# untitled.net
KiCad netlist of a schematic drawn in EAGLE
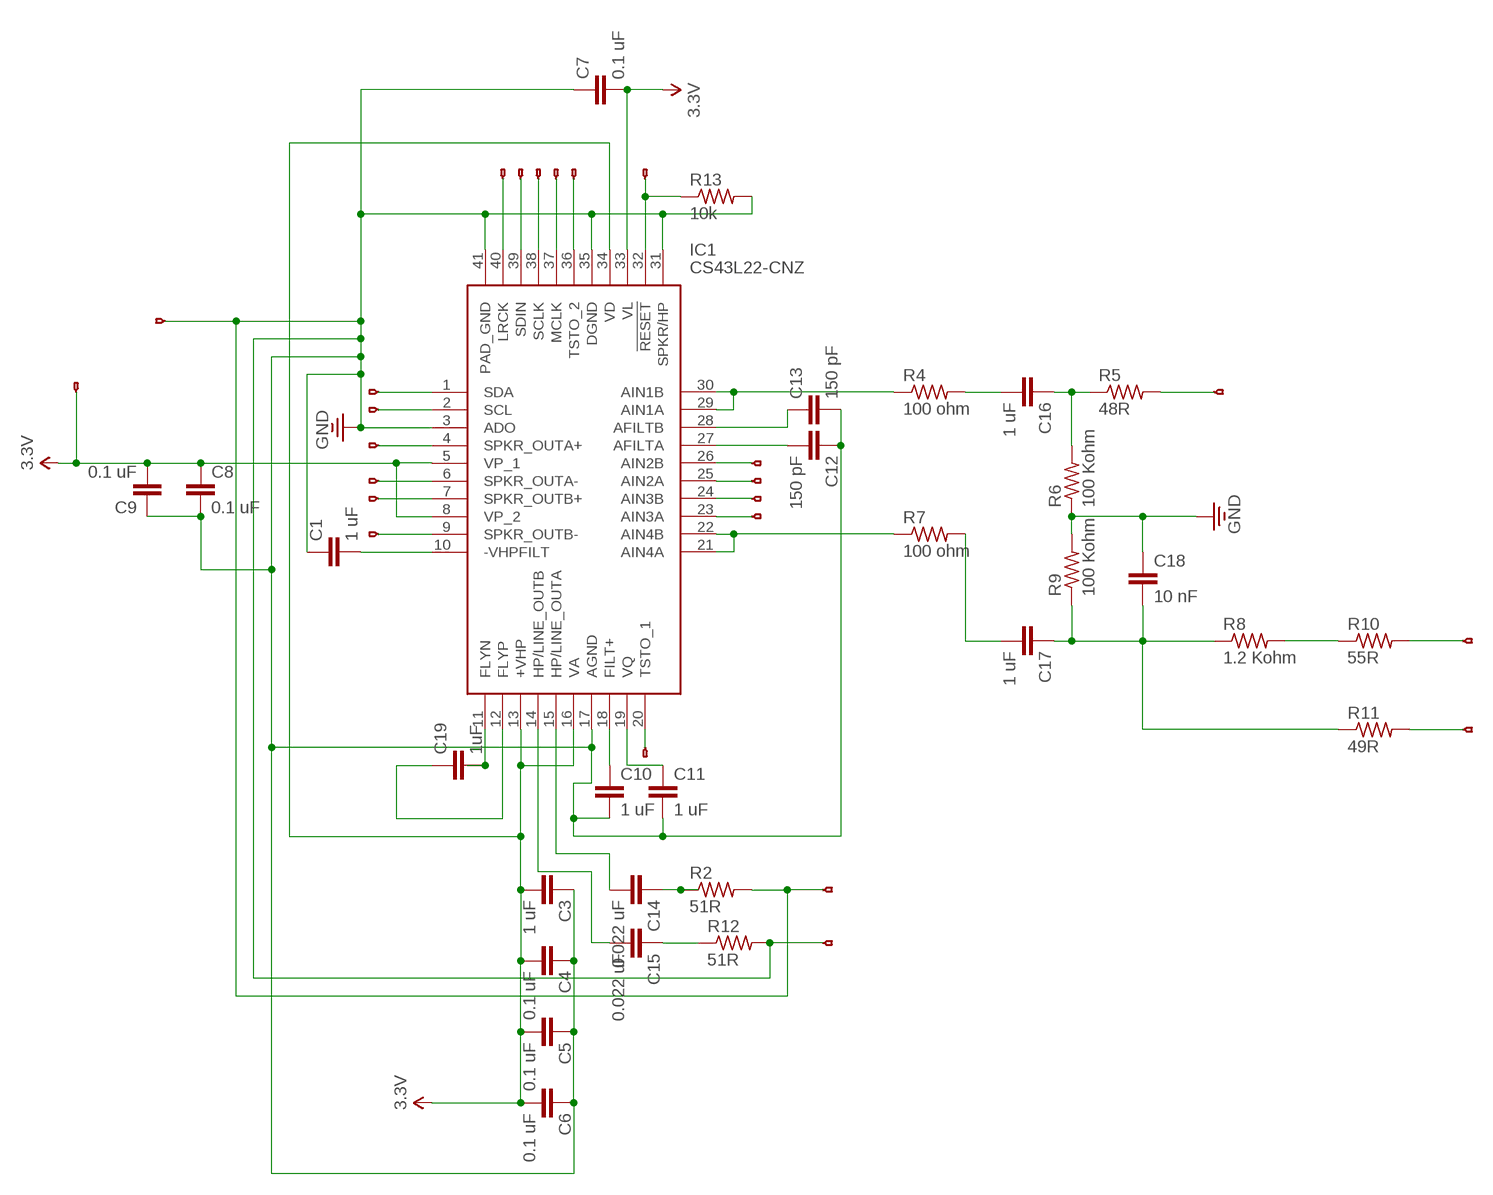
[diagram p0: schematic, sheet 1]

(export (version "E")
  (design (tool "Eeschema 10.0.6"))
  (components
    (comp (ref "C1")
      (value "1 uF")
      (footprint "eagle-import:CAP-PTH-SMALL-KIT")
      (libsource (lib "eagle-import") (part "CAPKIT"))
    )
    (comp (ref "C3")
      (value "1 uF")
      (footprint "eagle-import:CAP-PTH-SMALL-KIT")
      (libsource (lib "eagle-import") (part "CAPKIT"))
    )
    (comp (ref "C4")
      (value "0.1 uF")
      (footprint "eagle-import:CAP-PTH-SMALL-KIT")
      (libsource (lib "eagle-import") (part "CAPKIT"))
    )
    (comp (ref "C5")
      (value "0.1 uF")
      (footprint "eagle-import:CAP-PTH-SMALL-KIT")
      (libsource (lib "eagle-import") (part "CAPKIT"))
    )
    (comp (ref "C6")
      (value "0.1 uF")
      (footprint "eagle-import:CAP-PTH-SMALL-KIT")
      (libsource (lib "eagle-import") (part "CAPKIT"))
    )
    (comp (ref "C7")
      (value "0.1 uF")
      (footprint "eagle-import:CAP-PTH-SMALL-KIT")
      (libsource (lib "eagle-import") (part "CAPKIT"))
    )
    (comp (ref "C8")
      (value "0.1 uF")
      (footprint "eagle-import:CAP-PTH-SMALL-KIT")
      (libsource (lib "eagle-import") (part "CAPKIT"))
    )
    (comp (ref "C9")
      (value "0.1 uF")
      (footprint "eagle-import:CAP-PTH-SMALL-KIT")
      (libsource (lib "eagle-import") (part "CAPKIT"))
    )
    (comp (ref "C10")
      (value "1 uF")
      (footprint "eagle-import:CAP-PTH-SMALL-KIT")
      (libsource (lib "eagle-import") (part "CAPKIT"))
    )
    (comp (ref "C11")
      (value "1 uF")
      (footprint "eagle-import:CAP-PTH-SMALL-KIT")
      (libsource (lib "eagle-import") (part "CAPKIT"))
    )
    (comp (ref "C12")
      (value "150 pF")
      (footprint "eagle-import:CAP-PTH-SMALL-KIT")
      (libsource (lib "eagle-import") (part "CAPKIT"))
    )
    (comp (ref "C13")
      (value "150 pF")
      (footprint "eagle-import:CAP-PTH-SMALL-KIT")
      (libsource (lib "eagle-import") (part "CAPKIT"))
    )
    (comp (ref "C14")
      (value "0.022 uF")
      (footprint "eagle-import:CAP-PTH-SMALL-KIT")
      (libsource (lib "eagle-import") (part "CAPKIT"))
    )
    (comp (ref "C15")
      (value "0.022 uF")
      (footprint "eagle-import:CAP-PTH-SMALL-KIT")
      (libsource (lib "eagle-import") (part "CAPKIT"))
    )
    (comp (ref "C16")
      (value "1 uF")
      (footprint "eagle-import:CAP-PTH-SMALL-KIT")
      (libsource (lib "eagle-import") (part "CAPKIT"))
    )
    (comp (ref "C17")
      (value "1 uF")
      (footprint "eagle-import:CAP-PTH-SMALL-KIT")
      (libsource (lib "eagle-import") (part "CAPKIT"))
    )
    (comp (ref "C18")
      (value "10 nF")
      (footprint "eagle-import:CAP-PTH-SMALL-KIT")
      (libsource (lib "eagle-import") (part "CAPKIT"))
    )
    (comp (ref "C19")
      (value "1uF")
      (footprint "eagle-import:C2.5-3")
      (libsource (lib "eagle-import") (part "C2,5-3"))
    )
    (comp (ref "IC1")
      (value "CS43L22-CNZ")
      (footprint "eagle-import:QFN50P600X600X100-41N")
      (fields
        (field (name "MOUSER_PART_NUMBER") "777-CS43L22-CNZ")
        (field (name "RS_PART_NUMBER") "7165851P")
      )
      (libsource (lib "eagle-import") (part "CS43L22-CNZ"))
    )
    (comp (ref "JP1")
      (value "HEADERHOLE-HEADERHOLE")
      (footprint "eagle-import:1X1-HEADER-HOLE")
      (libsource (lib "eagle-import") (part "HEADERHOLE-HEADERHOLE"))
    )
    (comp (ref "JP2")
      (value "HEADERHOLE-HEADERHOLE")
      (footprint "eagle-import:1X1-HEADER-HOLE")
      (libsource (lib "eagle-import") (part "HEADERHOLE-HEADERHOLE"))
    )
    (comp (ref "JP3")
      (value "HEADERHOLE-HEADERHOLE")
      (footprint "eagle-import:1X1-HEADER-HOLE")
      (libsource (lib "eagle-import") (part "HEADERHOLE-HEADERHOLE"))
    )
    (comp (ref "JP4")
      (value "HEADERHOLE-HEADERHOLE")
      (footprint "eagle-import:1X1-HEADER-HOLE")
      (libsource (lib "eagle-import") (part "HEADERHOLE-HEADERHOLE"))
    )
    (comp (ref "JP5")
      (value "HEADERHOLE-HEADERHOLE")
      (footprint "eagle-import:1X1-HEADER-HOLE")
      (libsource (lib "eagle-import") (part "HEADERHOLE-HEADERHOLE"))
    )
    (comp (ref "JP6")
      (value "HEADERHOLE-HEADERHOLE")
      (footprint "eagle-import:1X1-HEADER-HOLE")
      (libsource (lib "eagle-import") (part "HEADERHOLE-HEADERHOLE"))
    )
    (comp (ref "JP7")
      (value "HEADERHOLE-HEADERHOLE")
      (footprint "eagle-import:1X1-HEADER-HOLE")
      (libsource (lib "eagle-import") (part "HEADERHOLE-HEADERHOLE"))
    )
    (comp (ref "JP8")
      (value "HEADERHOLE-HEADERHOLE")
      (footprint "eagle-import:1X1-HEADER-HOLE")
      (libsource (lib "eagle-import") (part "HEADERHOLE-HEADERHOLE"))
    )
    (comp (ref "JP9")
      (value "HEADERHOLE-HEADERHOLE")
      (footprint "eagle-import:1X1-HEADER-HOLE")
      (libsource (lib "eagle-import") (part "HEADERHOLE-HEADERHOLE"))
    )
    (comp (ref "JP10")
      (value "HEADERHOLE-HEADERHOLE")
      (footprint "eagle-import:1X1-HEADER-HOLE")
      (libsource (lib "eagle-import") (part "HEADERHOLE-HEADERHOLE"))
    )
    (comp (ref "JP11")
      (value "HEADERHOLE-HEADERHOLE")
      (footprint "eagle-import:1X1-HEADER-HOLE")
      (libsource (lib "eagle-import") (part "HEADERHOLE-HEADERHOLE"))
    )
    (comp (ref "JP12")
      (value "HEADERHOLE-HEADERHOLE")
      (footprint "eagle-import:1X1-HEADER-HOLE")
      (libsource (lib "eagle-import") (part "HEADERHOLE-HEADERHOLE"))
    )
    (comp (ref "JP13")
      (value "HEADERHOLE-HEADERHOLE")
      (footprint "eagle-import:1X1-HEADER-HOLE")
      (libsource (lib "eagle-import") (part "HEADERHOLE-HEADERHOLE"))
    )
    (comp (ref "JP14")
      (value "HEADERHOLE-HEADERHOLE")
      (footprint "eagle-import:1X1-HEADER-HOLE")
      (libsource (lib "eagle-import") (part "HEADERHOLE-HEADERHOLE"))
    )
    (comp (ref "JP15")
      (value "HEADERHOLE-HEADERHOLE")
      (footprint "eagle-import:1X1-HEADER-HOLE")
      (libsource (lib "eagle-import") (part "HEADERHOLE-HEADERHOLE"))
    )
    (comp (ref "JP16")
      (value "HEADERHOLE-HEADERHOLE")
      (footprint "eagle-import:1X1-HEADER-HOLE")
      (libsource (lib "eagle-import") (part "HEADERHOLE-HEADERHOLE"))
    )
    (comp (ref "JP17")
      (value "HEADERHOLE-HEADERHOLE")
      (footprint "eagle-import:1X1-HEADER-HOLE")
      (libsource (lib "eagle-import") (part "HEADERHOLE-HEADERHOLE"))
    )
    (comp (ref "JP18")
      (value "HEADERHOLE-HEADERHOLE")
      (footprint "eagle-import:1X1-HEADER-HOLE")
      (libsource (lib "eagle-import") (part "HEADERHOLE-HEADERHOLE"))
    )
    (comp (ref "JP19")
      (value "HEADERHOLE-HEADERHOLE")
      (footprint "eagle-import:1X1-HEADER-HOLE")
      (libsource (lib "eagle-import") (part "HEADERHOLE-HEADERHOLE"))
    )
    (comp (ref "JP20")
      (value "HEADERHOLE-HEADERHOLE")
      (footprint "eagle-import:1X1-HEADER-HOLE")
      (libsource (lib "eagle-import") (part "HEADERHOLE-HEADERHOLE"))
    )
    (comp (ref "JP21")
      (value "HEADERHOLE-HEADERHOLE")
      (footprint "eagle-import:1X1-HEADER-HOLE")
      (libsource (lib "eagle-import") (part "HEADERHOLE-HEADERHOLE"))
    )
    (comp (ref "JP22")
      (value "HEADERHOLE-HEADERHOLE")
      (footprint "eagle-import:1X1-HEADER-HOLE")
      (libsource (lib "eagle-import") (part "HEADERHOLE-HEADERHOLE"))
    )
    (comp (ref "JP23")
      (value "HEADERHOLE-HEADERHOLE")
      (footprint "eagle-import:1X1-HEADER-HOLE")
      (libsource (lib "eagle-import") (part "HEADERHOLE-HEADERHOLE"))
    )
    (comp (ref "JP24")
      (value "HEADERHOLE-HEADERHOLE")
      (footprint "eagle-import:1X1-HEADER-HOLE")
      (libsource (lib "eagle-import") (part "HEADERHOLE-HEADERHOLE"))
    )
    (comp (ref "R2")
      (value "51R")
      (footprint "eagle-import:0204V")
      (libsource (lib "eagle-import") (part "R-US_0204/2V"))
    )
    (comp (ref "R4")
      (value "100 ohm")
      (footprint "eagle-import:0204V")
      (libsource (lib "eagle-import") (part "R-US_0204/2V"))
    )
    (comp (ref "R5")
      (value "48R")
      (footprint "eagle-import:0204V")
      (libsource (lib "eagle-import") (part "R-US_0204/2V"))
    )
    (comp (ref "R6")
      (value "100 Kohm")
      (footprint "eagle-import:0204V")
      (libsource (lib "eagle-import") (part "R-US_0204/2V"))
    )
    (comp (ref "R7")
      (value "100 ohm")
      (footprint "eagle-import:0204V")
      (libsource (lib "eagle-import") (part "R-US_0204/2V"))
    )
    (comp (ref "R8")
      (value "1.2 Kohm")
      (footprint "eagle-import:0204V")
      (libsource (lib "eagle-import") (part "R-US_0204/2V"))
    )
    (comp (ref "R9")
      (value "100 Kohm")
      (footprint "eagle-import:0204V")
      (libsource (lib "eagle-import") (part "R-US_0204/2V"))
    )
    (comp (ref "R10")
      (value "55R")
      (footprint "eagle-import:0204V")
      (libsource (lib "eagle-import") (part "R-US_0204/2V"))
    )
    (comp (ref "R11")
      (value "49R")
      (footprint "eagle-import:0204V")
      (libsource (lib "eagle-import") (part "R-US_0204/2V"))
    )
    (comp (ref "R12")
      (value "51R")
      (footprint "eagle-import:0204V")
      (libsource (lib "eagle-import") (part "R-US_0204/2V"))
    )
    (comp (ref "R13")
      (value "10k")
      (footprint "eagle-import:0204V")
      (libsource (lib "eagle-import") (part "R-US_0204/2V"))
    )
  )
  (nets
    (net (code "1") (name "3.3V") (class "Default")
      (node (ref "C3") (pin "2") (pinfunction "2_2") (pintype "passive"))
      (node (ref "C4") (pin "2") (pinfunction "2_2") (pintype "passive"))
      (node (ref "C5") (pin "2") (pinfunction "2_2") (pintype "passive"))
      (node (ref "C6") (pin "2") (pinfunction "2_2") (pintype "passive"))
      (node (ref "C7") (pin "2") (pinfunction "2_2") (pintype "passive"))
      (node (ref "C8") (pin "1") (pinfunction "1_1") (pintype "passive"))
      (node (ref "C9") (pin "2") (pinfunction "2_2") (pintype "passive"))
      (node (ref "IC1") (pin "13") (pinfunction "+VHP_13") (pintype "bidirectional"))
      (node (ref "IC1") (pin "16") (pinfunction "VA_16") (pintype "bidirectional"))
      (node (ref "IC1") (pin "33") (pinfunction "VL_33") (pintype "bidirectional"))
      (node (ref "IC1") (pin "34") (pinfunction "VD_34") (pintype "bidirectional"))
      (node (ref "IC1") (pin "5") (pinfunction "VP_1_5") (pintype "bidirectional"))
      (node (ref "IC1") (pin "8") (pinfunction "VP_2_8") (pintype "bidirectional"))
      (node (ref "JP24") (pin "1") (pinfunction "P$1_1") (pintype "bidirectional"))
    )
    (net (code "2") (name "GND") (class "Default")
      (node (ref "C1") (pin "1") (pinfunction "1_1") (pintype "passive"))
      (node (ref "C10") (pin "2") (pinfunction "2_2") (pintype "passive"))
      (node (ref "C11") (pin "2") (pinfunction "2_2") (pintype "passive"))
      (node (ref "C12") (pin "1") (pinfunction "1_1") (pintype "passive"))
      (node (ref "C13") (pin "2") (pinfunction "2_2") (pintype "passive"))
      (node (ref "C18") (pin "1") (pinfunction "1_1") (pintype "passive"))
      (node (ref "C3") (pin "1") (pinfunction "1_1") (pintype "passive"))
      (node (ref "C4") (pin "1") (pinfunction "1_1") (pintype "passive"))
      (node (ref "C5") (pin "1") (pinfunction "1_1") (pintype "passive"))
      (node (ref "C6") (pin "1") (pinfunction "1_1") (pintype "passive"))
      (node (ref "C7") (pin "1") (pinfunction "1_1") (pintype "passive"))
      (node (ref "C8") (pin "2") (pinfunction "2_2") (pintype "passive"))
      (node (ref "C9") (pin "1") (pinfunction "1_1") (pintype "passive"))
      (node (ref "IC1") (pin "17") (pinfunction "AGND_17") (pintype "bidirectional"))
      (node (ref "IC1") (pin "3") (pinfunction "ADO_3") (pintype "bidirectional"))
      (node (ref "IC1") (pin "31") (pinfunction "SPKR/HP_31") (pintype "bidirectional"))
      (node (ref "IC1") (pin "35") (pinfunction "DGND_35") (pintype "bidirectional"))
      (node (ref "IC1") (pin "41") (pinfunction "PAD_GND_41") (pintype "bidirectional"))
      (node (ref "JP23") (pin "1") (pinfunction "P$1_1") (pintype "bidirectional"))
      (node (ref "JP8") (pin "1") (pinfunction "P$1_1") (pintype "bidirectional"))
      (node (ref "JP9") (pin "1") (pinfunction "P$1_1") (pintype "bidirectional"))
      (node (ref "R12") (pin "2") (pinfunction "2_2") (pintype "passive"))
      (node (ref "R13") (pin "2") (pinfunction "2_2") (pintype "passive"))
      (node (ref "R2") (pin "2") (pinfunction "2_2") (pintype "passive"))
      (node (ref "R6") (pin "1") (pinfunction "1_1") (pintype "passive"))
      (node (ref "R9") (pin "2") (pinfunction "2_2") (pintype "passive"))
    )
    (net (code "3") (name "Net-(C14-Pad1)") (class "Default")
      (node (ref "C14") (pin "1") (pinfunction "1_1") (pintype "passive"))
      (node (ref "R2") (pin "1") (pinfunction "1_1") (pintype "passive"))
    )
    (net (code "4") (name "Net-(C15-Pad1)") (class "Default")
      (node (ref "C15") (pin "1") (pinfunction "1_1") (pintype "passive"))
      (node (ref "R12") (pin "1") (pinfunction "1_1") (pintype "passive"))
    )
    (net (code "5") (name "Net-(C16-Pad1)") (class "Default")
      (node (ref "C16") (pin "1") (pinfunction "1_1") (pintype "passive"))
      (node (ref "R5") (pin "1") (pinfunction "1_1") (pintype "passive"))
      (node (ref "R6") (pin "2") (pinfunction "2_2") (pintype "passive"))
    )
    (net (code "6") (name "Net-(C16-Pad2)") (class "Default")
      (node (ref "C16") (pin "2") (pinfunction "2_2") (pintype "passive"))
      (node (ref "R4") (pin "2") (pinfunction "2_2") (pintype "passive"))
    )
    (net (code "7") (name "Net-(C17-Pad1)") (class "Default")
      (node (ref "C17") (pin "1") (pinfunction "1_1") (pintype "passive"))
      (node (ref "C18") (pin "2") (pinfunction "2_2") (pintype "passive"))
      (node (ref "R11") (pin "1") (pinfunction "1_1") (pintype "passive"))
      (node (ref "R8") (pin "1") (pinfunction "1_1") (pintype "passive"))
      (node (ref "R9") (pin "1") (pinfunction "1_1") (pintype "passive"))
    )
    (net (code "8") (name "Net-(C17-Pad2)") (class "Default")
      (node (ref "C17") (pin "2") (pinfunction "2_2") (pintype "passive"))
      (node (ref "R7") (pin "2") (pinfunction "2_2") (pintype "passive"))
    )
    (net (code "9") (name "Net-(IC1--VHPFILT)") (class "Default")
      (node (ref "C1") (pin "2") (pinfunction "2_2") (pintype "passive"))
      (node (ref "IC1") (pin "10") (pinfunction "-VHPFILT_10") (pintype "bidirectional"))
    )
    (net (code "10") (name "Net-(IC1-AFILTA)") (class "Default")
      (node (ref "C12") (pin "2") (pinfunction "2_2") (pintype "passive"))
      (node (ref "IC1") (pin "27") (pinfunction "AFILTA_27") (pintype "bidirectional"))
    )
    (net (code "11") (name "Net-(IC1-AFILTB)") (class "Default")
      (node (ref "C13") (pin "1") (pinfunction "1_1") (pintype "passive"))
      (node (ref "IC1") (pin "28") (pinfunction "AFILTB_28") (pintype "bidirectional"))
    )
    (net (code "12") (name "Net-(IC1-AIN1A)") (class "Default")
      (node (ref "IC1") (pin "29") (pinfunction "AIN1A_29") (pintype "bidirectional"))
      (node (ref "IC1") (pin "30") (pinfunction "AIN1B_30") (pintype "bidirectional"))
      (node (ref "R4") (pin "1") (pinfunction "1_1") (pintype "passive"))
    )
    (net (code "13") (name "Net-(IC1-AIN2A)") (class "Default")
      (node (ref "IC1") (pin "25") (pinfunction "AIN2A_25") (pintype "bidirectional"))
      (node (ref "JP16") (pin "1") (pinfunction "P$1_1") (pintype "bidirectional"))
    )
    (net (code "14") (name "Net-(IC1-AIN2B)") (class "Default")
      (node (ref "IC1") (pin "26") (pinfunction "AIN2B_26") (pintype "bidirectional"))
      (node (ref "JP17") (pin "1") (pinfunction "P$1_1") (pintype "bidirectional"))
    )
    (net (code "15") (name "Net-(IC1-AIN3A)") (class "Default")
      (node (ref "IC1") (pin "23") (pinfunction "AIN3A_23") (pintype "bidirectional"))
      (node (ref "JP14") (pin "1") (pinfunction "P$1_1") (pintype "bidirectional"))
    )
    (net (code "16") (name "Net-(IC1-AIN3B)") (class "Default")
      (node (ref "IC1") (pin "24") (pinfunction "AIN3B_24") (pintype "bidirectional"))
      (node (ref "JP15") (pin "1") (pinfunction "P$1_1") (pintype "bidirectional"))
    )
    (net (code "17") (name "Net-(IC1-AIN4A)") (class "Default")
      (node (ref "IC1") (pin "21") (pinfunction "AIN4A_21") (pintype "bidirectional"))
      (node (ref "IC1") (pin "22") (pinfunction "AIN4B_22") (pintype "bidirectional"))
      (node (ref "R7") (pin "1") (pinfunction "1_1") (pintype "passive"))
    )
    (net (code "18") (name "Net-(IC1-FILT+)") (class "Default")
      (node (ref "C10") (pin "1") (pinfunction "1_1") (pintype "passive"))
      (node (ref "IC1") (pin "18") (pinfunction "FILT+_18") (pintype "bidirectional"))
    )
    (net (code "19") (name "Net-(IC1-FLYN)") (class "Default")
      (node (ref "C19") (pin "2") (pinfunction "2_2") (pintype "passive"))
      (node (ref "IC1") (pin "11") (pinfunction "FLYN_11") (pintype "bidirectional"))
    )
    (net (code "20") (name "Net-(IC1-FLYP)") (class "Default")
      (node (ref "C19") (pin "1") (pinfunction "1_1") (pintype "passive"))
      (node (ref "IC1") (pin "12") (pinfunction "FLYP_12") (pintype "bidirectional"))
    )
    (net (code "21") (name "Net-(IC1-HP{slash}LINE_OUTA)") (class "Default")
      (node (ref "C14") (pin "2") (pinfunction "2_2") (pintype "passive"))
      (node (ref "IC1") (pin "15") (pinfunction "HP/LINE_OUTA_15") (pintype "bidirectional"))
    )
    (net (code "22") (name "Net-(IC1-HP{slash}LINE_OUTB)") (class "Default")
      (node (ref "C15") (pin "2") (pinfunction "2_2") (pintype "passive"))
      (node (ref "IC1") (pin "14") (pinfunction "HP/LINE_OUTB_14") (pintype "bidirectional"))
    )
    (net (code "23") (name "Net-(IC1-LRCK)") (class "Default")
      (node (ref "IC1") (pin "40") (pinfunction "LRCK_40") (pintype "bidirectional"))
      (node (ref "JP6") (pin "1") (pinfunction "P$1_1") (pintype "bidirectional"))
    )
    (net (code "24") (name "Net-(IC1-MCLK)") (class "Default")
      (node (ref "IC1") (pin "37") (pinfunction "MCLK_37") (pintype "bidirectional"))
      (node (ref "JP3") (pin "1") (pinfunction "P$1_1") (pintype "bidirectional"))
    )
    (net (code "25") (name "Net-(IC1-SCL)") (class "Default")
      (node (ref "IC1") (pin "2") (pinfunction "SCL_2") (pintype "bidirectional"))
      (node (ref "JP2") (pin "1") (pinfunction "P$1_1") (pintype "bidirectional"))
    )
    (net (code "26") (name "Net-(IC1-SCLK)") (class "Default")
      (node (ref "IC1") (pin "38") (pinfunction "SCLK_38") (pintype "bidirectional"))
      (node (ref "JP4") (pin "1") (pinfunction "P$1_1") (pintype "bidirectional"))
    )
    (net (code "27") (name "Net-(IC1-SDA)") (class "Default")
      (node (ref "IC1") (pin "1") (pinfunction "SDA_1") (pintype "bidirectional"))
      (node (ref "JP1") (pin "1") (pinfunction "P$1_1") (pintype "bidirectional"))
    )
    (net (code "28") (name "Net-(IC1-SDIN)") (class "Default")
      (node (ref "IC1") (pin "39") (pinfunction "SDIN_39") (pintype "bidirectional"))
      (node (ref "JP5") (pin "1") (pinfunction "P$1_1") (pintype "bidirectional"))
    )
    (net (code "29") (name "Net-(IC1-SPKR_OUTA+)") (class "Default")
      (node (ref "IC1") (pin "4") (pinfunction "SPKR_OUTA+_4") (pintype "bidirectional"))
      (node (ref "JP10") (pin "1") (pinfunction "P$1_1") (pintype "bidirectional"))
    )
    (net (code "30") (name "Net-(IC1-SPKR_OUTA-)") (class "Default")
      (node (ref "IC1") (pin "6") (pinfunction "SPKR_OUTA-_6") (pintype "bidirectional"))
      (node (ref "JP11") (pin "1") (pinfunction "P$1_1") (pintype "bidirectional"))
    )
    (net (code "31") (name "Net-(IC1-SPKR_OUTB+)") (class "Default")
      (node (ref "IC1") (pin "7") (pinfunction "SPKR_OUTB+_7") (pintype "bidirectional"))
      (node (ref "JP12") (pin "1") (pinfunction "P$1_1") (pintype "bidirectional"))
    )
    (net (code "32") (name "Net-(IC1-SPKR_OUTB-)") (class "Default")
      (node (ref "IC1") (pin "9") (pinfunction "SPKR_OUTB-_9") (pintype "bidirectional"))
      (node (ref "JP13") (pin "1") (pinfunction "P$1_1") (pintype "bidirectional"))
    )
    (net (code "33") (name "Net-(IC1-TSTO_1)") (class "Default")
      (node (ref "IC1") (pin "20") (pinfunction "TSTO_1_20") (pintype "bidirectional"))
      (node (ref "JP18") (pin "1") (pinfunction "P$1_1") (pintype "bidirectional"))
    )
    (net (code "34") (name "Net-(IC1-TSTO_2)") (class "Default")
      (node (ref "IC1") (pin "36") (pinfunction "TSTO_2_36") (pintype "bidirectional"))
      (node (ref "JP19") (pin "1") (pinfunction "P$1_1") (pintype "bidirectional"))
    )
    (net (code "35") (name "Net-(IC1-VQ)") (class "Default")
      (node (ref "C11") (pin "1") (pinfunction "1_1") (pintype "passive"))
      (node (ref "IC1") (pin "19") (pinfunction "VQ_19") (pintype "bidirectional"))
    )
    (net (code "36") (name "Net-(IC1-~{RESET})") (class "Default")
      (node (ref "IC1") (pin "32") (pinfunction "~{RESET}_32") (pintype "bidirectional"))
      (node (ref "JP7") (pin "1") (pinfunction "P$1_1") (pintype "bidirectional"))
      (node (ref "R13") (pin "1") (pinfunction "1_1") (pintype "passive"))
    )
    (net (code "37") (name "Net-(JP20-P$1)") (class "Default")
      (node (ref "JP20") (pin "1") (pinfunction "P$1_1") (pintype "bidirectional"))
      (node (ref "R5") (pin "2") (pinfunction "2_2") (pintype "passive"))
    )
    (net (code "38") (name "Net-(JP21-P$1)") (class "Default")
      (node (ref "JP21") (pin "1") (pinfunction "P$1_1") (pintype "bidirectional"))
      (node (ref "R10") (pin "2") (pinfunction "2_2") (pintype "passive"))
    )
    (net (code "39") (name "Net-(JP22-P$1)") (class "Default")
      (node (ref "JP22") (pin "1") (pinfunction "P$1_1") (pintype "bidirectional"))
      (node (ref "R11") (pin "2") (pinfunction "2_2") (pintype "passive"))
    )
    (net (code "40") (name "Net-(R10-Pad1)") (class "Default")
      (node (ref "R10") (pin "1") (pinfunction "1_1") (pintype "passive"))
      (node (ref "R8") (pin "2") (pinfunction "2_2") (pintype "passive"))
    )
  )
)
